# Procesador_Auxiliar.net
KiCad netlist of a schematic drawn in Altium Designer
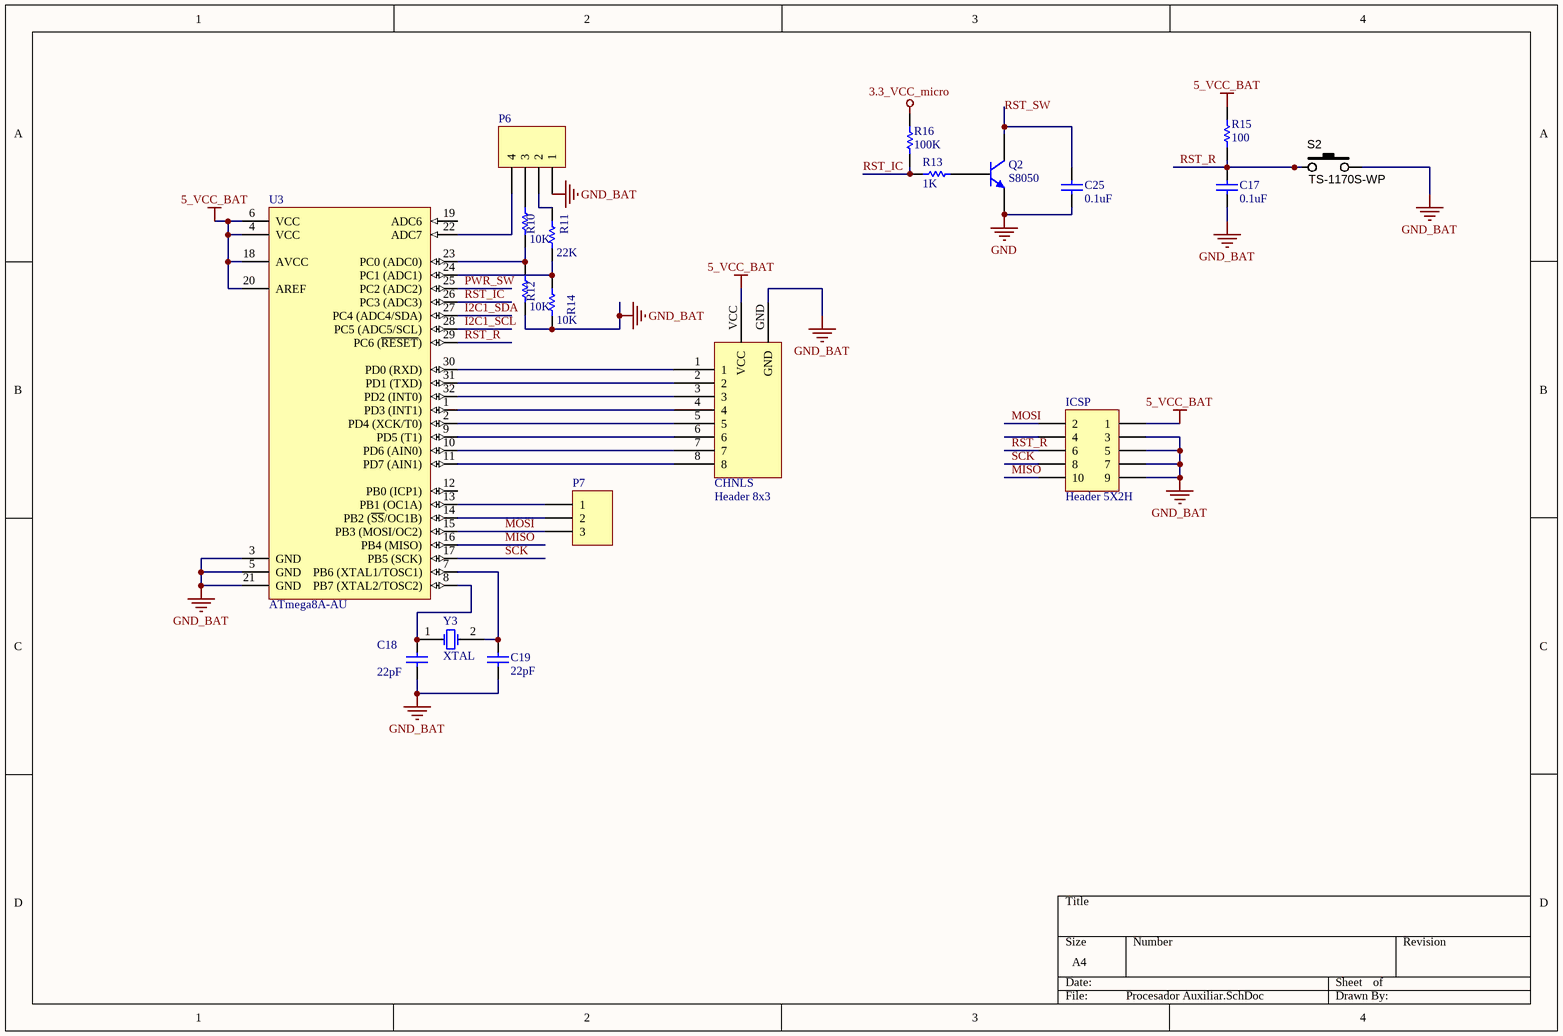
[diagram p0: Procesador Auxiliar.SchDoc]

(export (version "E")
  (design (tool "Eeschema 10.0.6"))
  (components
    (comp (ref "C17")
      (value "0.1uF")
      (footprint "C0805")
      (description "Capacitor")
      (fields (field (name "Comment") "Cap") (field (name "PUBLISHER") "Altium Limited"))
      (libsource (lib "Miscellaneous Devices") (part "Cap"))
    )
    (comp (ref "C18")
      (value "22pF")
      (footprint "6-0805_L")
      (description "Capacitor")
      (fields (field (name "Comment") "Cap Pol1") (field (name "PUBLISHER") "Altium Limited"))
      (libsource (lib "Miscellaneous Devices") (part "Cap"))
    )
    (comp (ref "C19")
      (value "22pF")
      (footprint "6-0805_L")
      (description "Capacitor")
      (fields (field (name "Comment") "Cap Pol1") (field (name "PUBLISHER") "Altium Limited"))
      (libsource (lib "Miscellaneous Devices") (part "Cap"))
    )
    (comp (ref "C25")
      (value "0.1uF")
      (footprint "C0805")
      (description "Capacitor")
      (fields (field (name "Comment") "Cap") (field (name "PUBLISHER") "Altium Limited"))
      (libsource (lib "Miscellaneous Devices") (part "Cap"))
    )
    (comp (ref "CHNLS")
      (value "Header 8x3")
      (footprint "Header 8x3_mirror")
      (libsource (lib "Conector") (part "Header 8x3"))
    )
    (comp (ref "ICSP")
      (value "Header 5X2H")
      (footprint "HDR2X5")
      (description "Header, 5-Pin, Dual row, Right Angle")
      (fields (field (name "PUBLISHER") "Altium Limited"))
      (libsource (lib "Miscellaneous Connectors") (part "Header 5X2H"))
    )
    (comp (ref "P6")
      (value "Header 4")
      (footprint "HDR1X4")
      (description "Header, 4-Pin")
      (fields (field (name "PUBLISHER") "Altium Limited"))
      (libsource (lib "Miscellaneous Connectors") (part "Header 4"))
    )
    (comp (ref "P7")
      (value "Header 3")
      (footprint "HDR1X3")
      (description "Header, 3-Pin")
      (fields (field (name "PUBLISHER") "Altium Limited"))
      (libsource (lib "Miscellaneous Connectors") (part "Header 3"))
    )
    (comp (ref "Q2")
      (value "S8050")
      (footprint "SOT23-3")
      (description "NPN SMD General Purpose Amplifier")
      (fields (field (name "PUBLISHER") "Altium Limited"))
      (libsource (lib "Libreria General") (part "S8050"))
    )
    (comp (ref "R10")
      (value "10K")
      (footprint "C0805")
      (description "Resistor")
      (fields (field (name "Comment") "Res1") (field (name "PUBLISHER") "Altium Limited"))
      (libsource (lib "Miscellaneous Devices") (part "Res1"))
    )
    (comp (ref "R11")
      (value "22K")
      (footprint "C0805")
      (description "Resistor")
      (fields (field (name "Comment") "Res1") (field (name "PUBLISHER") "Altium Limited"))
      (libsource (lib "Miscellaneous Devices") (part "Res1"))
    )
    (comp (ref "R12")
      (value "10K")
      (footprint "C1206")
      (description "Resistor")
      (fields (field (name "Comment") "Res1") (field (name "PUBLISHER") "Altium Limited"))
      (libsource (lib "Miscellaneous Devices") (part "Res1"))
    )
    (comp (ref "R13")
      (value "1K")
      (footprint "C0805")
      (description "Resistor")
      (fields (field (name "Comment") "Res1") (field (name "PUBLISHER") "Altium Limited"))
      (libsource (lib "Miscellaneous Devices") (part "Res1"))
    )
    (comp (ref "R14")
      (value "10K")
      (footprint "C0805")
      (description "Resistor")
      (fields (field (name "Comment") "Res1") (field (name "PUBLISHER") "Altium Limited"))
      (libsource (lib "Miscellaneous Devices") (part "Res1"))
    )
    (comp (ref "R15")
      (value "100")
      (footprint "C0805")
      (description "Resistor")
      (fields (field (name "Comment") "Res1") (field (name "PUBLISHER") "Altium Limited"))
      (libsource (lib "Miscellaneous Devices") (part "Res1"))
    )
    (comp (ref "R16")
      (value "100K")
      (footprint "C0805")
      (description "Resistor")
      (fields (field (name "Comment") "Res1") (field (name "PUBLISHER") "Altium Limited"))
      (libsource (lib "Miscellaneous Devices") (part "Res1"))
    )
    (comp (ref "S2")
      (value "TS-1170S-WP")
      (footprint "TS-1170S")
      (description "Switch SMD Tact 7.0mm Stem")
      (libsource (lib "PBL - Switches") (part "SW_SMD_PB_7.0mm"))
    )
    (comp (ref "U3")
      (value "ATmega8A-AU")
      (footprint "Atmel Footprints:32A_N")
      (fields (field (name "PUBLISHER") "Altium Limited"))
      (libsource (lib "Atmel Microcontroller 8-Bit megaAVR") (part "ATmega8A-AU"))
    )
    (comp (ref "Y3")
      (value "XTAL")
      (footprint "4SMX")
      (description "Crystal Oscillator")
      (fields (field (name "PUBLISHER") "Altium Limited"))
      (libsource (lib "Miscellaneous Devices") (part "XTAL"))
    )
  )
  (nets
    (net (code "1") (name "/I2C1_SCL") (class "Default")
      (node (ref "U3") (pin "28") (pinfunction "PC5_(ADC5/SCL)_28") (pintype "bidirectional"))
    )
    (net (code "2") (name "/I2C1_SDA") (class "Default")
      (node (ref "U3") (pin "27") (pinfunction "PC4_(ADC4/SDA)_27") (pintype "bidirectional"))
    )
    (net (code "3") (name "/MISO") (class "Default")
      (node (ref "ICSP") (pin "10") (pinfunction "10_10") (pintype "passive"))
      (node (ref "U3") (pin "16") (pinfunction "PB4_(MISO)_16") (pintype "bidirectional"))
    )
    (net (code "4") (name "/MOSI") (class "Default")
      (node (ref "ICSP") (pin "2") (pinfunction "2_2") (pintype "passive"))
      (node (ref "P7") (pin "3") (pinfunction "3_3") (pintype "passive"))
      (node (ref "U3") (pin "15") (pinfunction "PB3_(MOSI/OC2)_15") (pintype "bidirectional"))
    )
    (net (code "5") (name "/PWR_SW") (class "Default")
      (node (ref "U3") (pin "25") (pinfunction "PC2_(ADC2)_25") (pintype "bidirectional"))
    )
    (net (code "6") (name "/RST_IC") (class "Default")
      (node (ref "R13") (pin "2") (pinfunction "2_2") (pintype "passive"))
      (node (ref "R16") (pin "2") (pinfunction "2_2") (pintype "passive"))
      (node (ref "U3") (pin "26") (pinfunction "PC3_(ADC3)_26") (pintype "bidirectional"))
    )
    (net (code "7") (name "/RST_R") (class "Default")
      (node (ref "C17") (pin "2") (pinfunction "2_2") (pintype "passive"))
      (node (ref "ICSP") (pin "6") (pinfunction "6_6") (pintype "passive"))
      (node (ref "R15") (pin "2") (pinfunction "2_2") (pintype "passive"))
      (node (ref "S2") (pin "1") (pintype "passive"))
      (node (ref "U3") (pin "29") (pinfunction "PC6_(~{RESET})_29") (pintype "bidirectional"))
    )
    (net (code "8") (name "/RST_SW") (class "Default")
      (node (ref "C25") (pin "2") (pinfunction "2_2") (pintype "passive"))
      (node (ref "Q2") (pin "3") (pinfunction "C_3") (pintype "passive"))
    )
    (net (code "9") (name "/SCK") (class "Default")
      (node (ref "ICSP") (pin "8") (pinfunction "8_8") (pintype "passive"))
      (node (ref "U3") (pin "17") (pinfunction "PB5_(SCK)_17") (pintype "bidirectional"))
    )
    (net (code "10") (name "3.3_VCC_micro") (class "Default")
      (node (ref "R16") (pin "1") (pinfunction "1_1") (pintype "passive"))
    )
    (net (code "11") (name "5_VCC_BAT") (class "Default")
      (node (ref "CHNLS") (pin "VCC") (pinfunction "VCC_VCC") (pintype "passive"))
      (node (ref "ICSP") (pin "1") (pinfunction "1_1") (pintype "passive"))
      (node (ref "R15") (pin "1") (pinfunction "1_1") (pintype "passive"))
      (node (ref "U3") (pin "18") (pinfunction "AVCC_18") (pintype "power_in"))
      (node (ref "U3") (pin "20") (pinfunction "AREF_20") (pintype "power_in"))
      (node (ref "U3") (pin "4") (pinfunction "VCC_4") (pintype "power_in"))
      (node (ref "U3") (pin "6") (pinfunction "VCC_6") (pintype "power_in"))
    )
    (net (code "12") (name "GND") (class "Default")
      (node (ref "C25") (pin "1") (pinfunction "1_1") (pintype "passive"))
      (node (ref "Q2") (pin "2") (pinfunction "E_2") (pintype "passive"))
    )
    (net (code "13") (name "GND_BAT") (class "Default")
      (node (ref "C17") (pin "1") (pinfunction "1_1") (pintype "passive"))
      (node (ref "C18") (pin "1") (pinfunction "1_1") (pintype "passive"))
      (node (ref "C19") (pin "1") (pinfunction "1_1") (pintype "passive"))
      (node (ref "CHNLS") (pin "GND") (pinfunction "GND_GND") (pintype "passive"))
      (node (ref "ICSP") (pin "3") (pinfunction "3_3") (pintype "passive"))
      (node (ref "ICSP") (pin "5") (pinfunction "5_5") (pintype "passive"))
      (node (ref "ICSP") (pin "7") (pinfunction "7_7") (pintype "passive"))
      (node (ref "ICSP") (pin "9") (pinfunction "9_9") (pintype "passive"))
      (node (ref "P6") (pin "1") (pinfunction "1_1") (pintype "passive"))
      (node (ref "R12") (pin "1") (pinfunction "1_1") (pintype "passive"))
      (node (ref "R14") (pin "1") (pinfunction "1_1") (pintype "passive"))
      (node (ref "S2") (pin "2") (pintype "passive"))
      (node (ref "U3") (pin "21") (pinfunction "GND_21") (pintype "power_in"))
      (node (ref "U3") (pin "3") (pinfunction "GND_3") (pintype "power_in"))
      (node (ref "U3") (pin "5") (pinfunction "GND_5") (pintype "power_in"))
    )
    (net (code "14") (name "Net-(P6-Pad2)") (class "Default")
      (node (ref "P6") (pin "2") (pinfunction "2_2") (pintype "passive"))
      (node (ref "R11") (pin "2") (pinfunction "2_2") (pintype "passive"))
    )
    (net (code "15") (name "Net-(P6-Pad3)") (class "Default")
      (node (ref "P6") (pin "3") (pinfunction "3_3") (pintype "passive"))
      (node (ref "R10") (pin "2") (pinfunction "2_2") (pintype "passive"))
    )
    (net (code "16") (name "Net-(Q2-B)") (class "Default")
      (node (ref "Q2") (pin "1") (pinfunction "B_1") (pintype "passive"))
      (node (ref "R13") (pin "1") (pinfunction "1_1") (pintype "passive"))
    )
    (net (code "17") (name "Net-(U3-ADC7)") (class "Default")
      (node (ref "P6") (pin "4") (pinfunction "4_4") (pintype "passive"))
      (node (ref "U3") (pin "22") (pinfunction "ADC7_22") (pintype "input"))
    )
    (net (code "18") (name "Net-(U3-PB1_(OC1A))") (class "Default")
      (node (ref "P7") (pin "1") (pinfunction "1_1") (pintype "passive"))
      (node (ref "U3") (pin "13") (pinfunction "PB1_(OC1A)_13") (pintype "bidirectional"))
    )
    (net (code "19") (name "Net-(U3-PB2_(~{SS}{slash}OC1B))") (class "Default")
      (node (ref "P7") (pin "2") (pinfunction "2_2") (pintype "passive"))
      (node (ref "U3") (pin "14") (pinfunction "PB2_(~{SS}/OC1B)_14") (pintype "bidirectional"))
    )
    (net (code "20") (name "Net-(U3-PB6_(XTAL1{slash}TOSC1))") (class "Default")
      (node (ref "C19") (pin "2") (pinfunction "2_2") (pintype "passive"))
      (node (ref "U3") (pin "7") (pinfunction "PB6_(XTAL1/TOSC1)_7") (pintype "bidirectional"))
      (node (ref "Y3") (pin "2") (pinfunction "OSC2_2") (pintype "passive"))
    )
    (net (code "21") (name "Net-(U3-PB7_(XTAL2{slash}TOSC2))") (class "Default")
      (node (ref "C18") (pin "2") (pinfunction "2_2") (pintype "passive"))
      (node (ref "U3") (pin "8") (pinfunction "PB7_(XTAL2/TOSC2)_8") (pintype "bidirectional"))
      (node (ref "Y3") (pin "1") (pinfunction "OSC1_1") (pintype "passive"))
    )
    (net (code "22") (name "Net-(U3-PC0_(ADC0))") (class "Default")
      (node (ref "R10") (pin "1") (pinfunction "1_1") (pintype "passive"))
      (node (ref "R12") (pin "2") (pinfunction "2_2") (pintype "passive"))
      (node (ref "U3") (pin "23") (pinfunction "PC0_(ADC0)_23") (pintype "bidirectional"))
    )
    (net (code "23") (name "Net-(U3-PC1_(ADC1))") (class "Default")
      (node (ref "R11") (pin "1") (pinfunction "1_1") (pintype "passive"))
      (node (ref "R14") (pin "2") (pinfunction "2_2") (pintype "passive"))
      (node (ref "U3") (pin "24") (pinfunction "PC1_(ADC1)_24") (pintype "bidirectional"))
    )
    (net (code "24") (name "Net-(U3-PD0_(RXD))") (class "Default")
      (node (ref "CHNLS") (pin "1") (pinfunction "1_1") (pintype "passive"))
      (node (ref "U3") (pin "30") (pinfunction "PD0_(RXD)_30") (pintype "bidirectional"))
    )
    (net (code "25") (name "Net-(U3-PD1_(TXD))") (class "Default")
      (node (ref "CHNLS") (pin "2") (pinfunction "2_2") (pintype "passive"))
      (node (ref "U3") (pin "31") (pinfunction "PD1_(TXD)_31") (pintype "bidirectional"))
    )
    (net (code "26") (name "Net-(U3-PD2_(INT0))") (class "Default")
      (node (ref "CHNLS") (pin "3") (pinfunction "3_3") (pintype "passive"))
      (node (ref "U3") (pin "32") (pinfunction "PD2_(INT0)_32") (pintype "bidirectional"))
    )
    (net (code "27") (name "Net-(U3-PD3_(INT1))") (class "Default")
      (node (ref "CHNLS") (pin "4") (pinfunction "4_4") (pintype "passive"))
      (node (ref "U3") (pin "1") (pinfunction "PD3_(INT1)_1") (pintype "bidirectional"))
    )
    (net (code "28") (name "Net-(U3-PD4_(XCK{slash}T0))") (class "Default")
      (node (ref "CHNLS") (pin "5") (pinfunction "5_5") (pintype "passive"))
      (node (ref "U3") (pin "2") (pinfunction "PD4_(XCK/T0)_2") (pintype "bidirectional"))
    )
    (net (code "29") (name "Net-(U3-PD5_(T1))") (class "Default")
      (node (ref "CHNLS") (pin "6") (pinfunction "6_6") (pintype "passive"))
      (node (ref "U3") (pin "9") (pinfunction "PD5_(T1)_9") (pintype "bidirectional"))
    )
    (net (code "30") (name "Net-(U3-PD6_(AIN0))") (class "Default")
      (node (ref "CHNLS") (pin "7") (pinfunction "7_7") (pintype "passive"))
      (node (ref "U3") (pin "10") (pinfunction "PD6_(AIN0)_10") (pintype "bidirectional"))
    )
    (net (code "31") (name "Net-(U3-PD7_(AIN1))") (class "Default")
      (node (ref "CHNLS") (pin "8") (pinfunction "8_8") (pintype "passive"))
      (node (ref "U3") (pin "11") (pinfunction "PD7_(AIN1)_11") (pintype "bidirectional"))
    )
    (net (code "32") (name "unconnected-(ICSP-Pad4)") (class "Default")
      (node (ref "ICSP") (pin "4") (pinfunction "4_4") (pintype "passive"))
    )
    (net (code "33") (name "unconnected-(U3-ADC6-Pad19)") (class "Default")
      (node (ref "U3") (pin "19") (pinfunction "ADC6_19") (pintype "input"))
    )
    (net (code "34") (name "unconnected-(U3-PB0_(ICP1)-Pad12)") (class "Default")
      (node (ref "U3") (pin "12") (pinfunction "PB0_(ICP1)_12") (pintype "bidirectional"))
    )
  )
)
